# Arduino_PC104_Adapter.net
KiCad netlist of a schematic drawn in Altium Designer
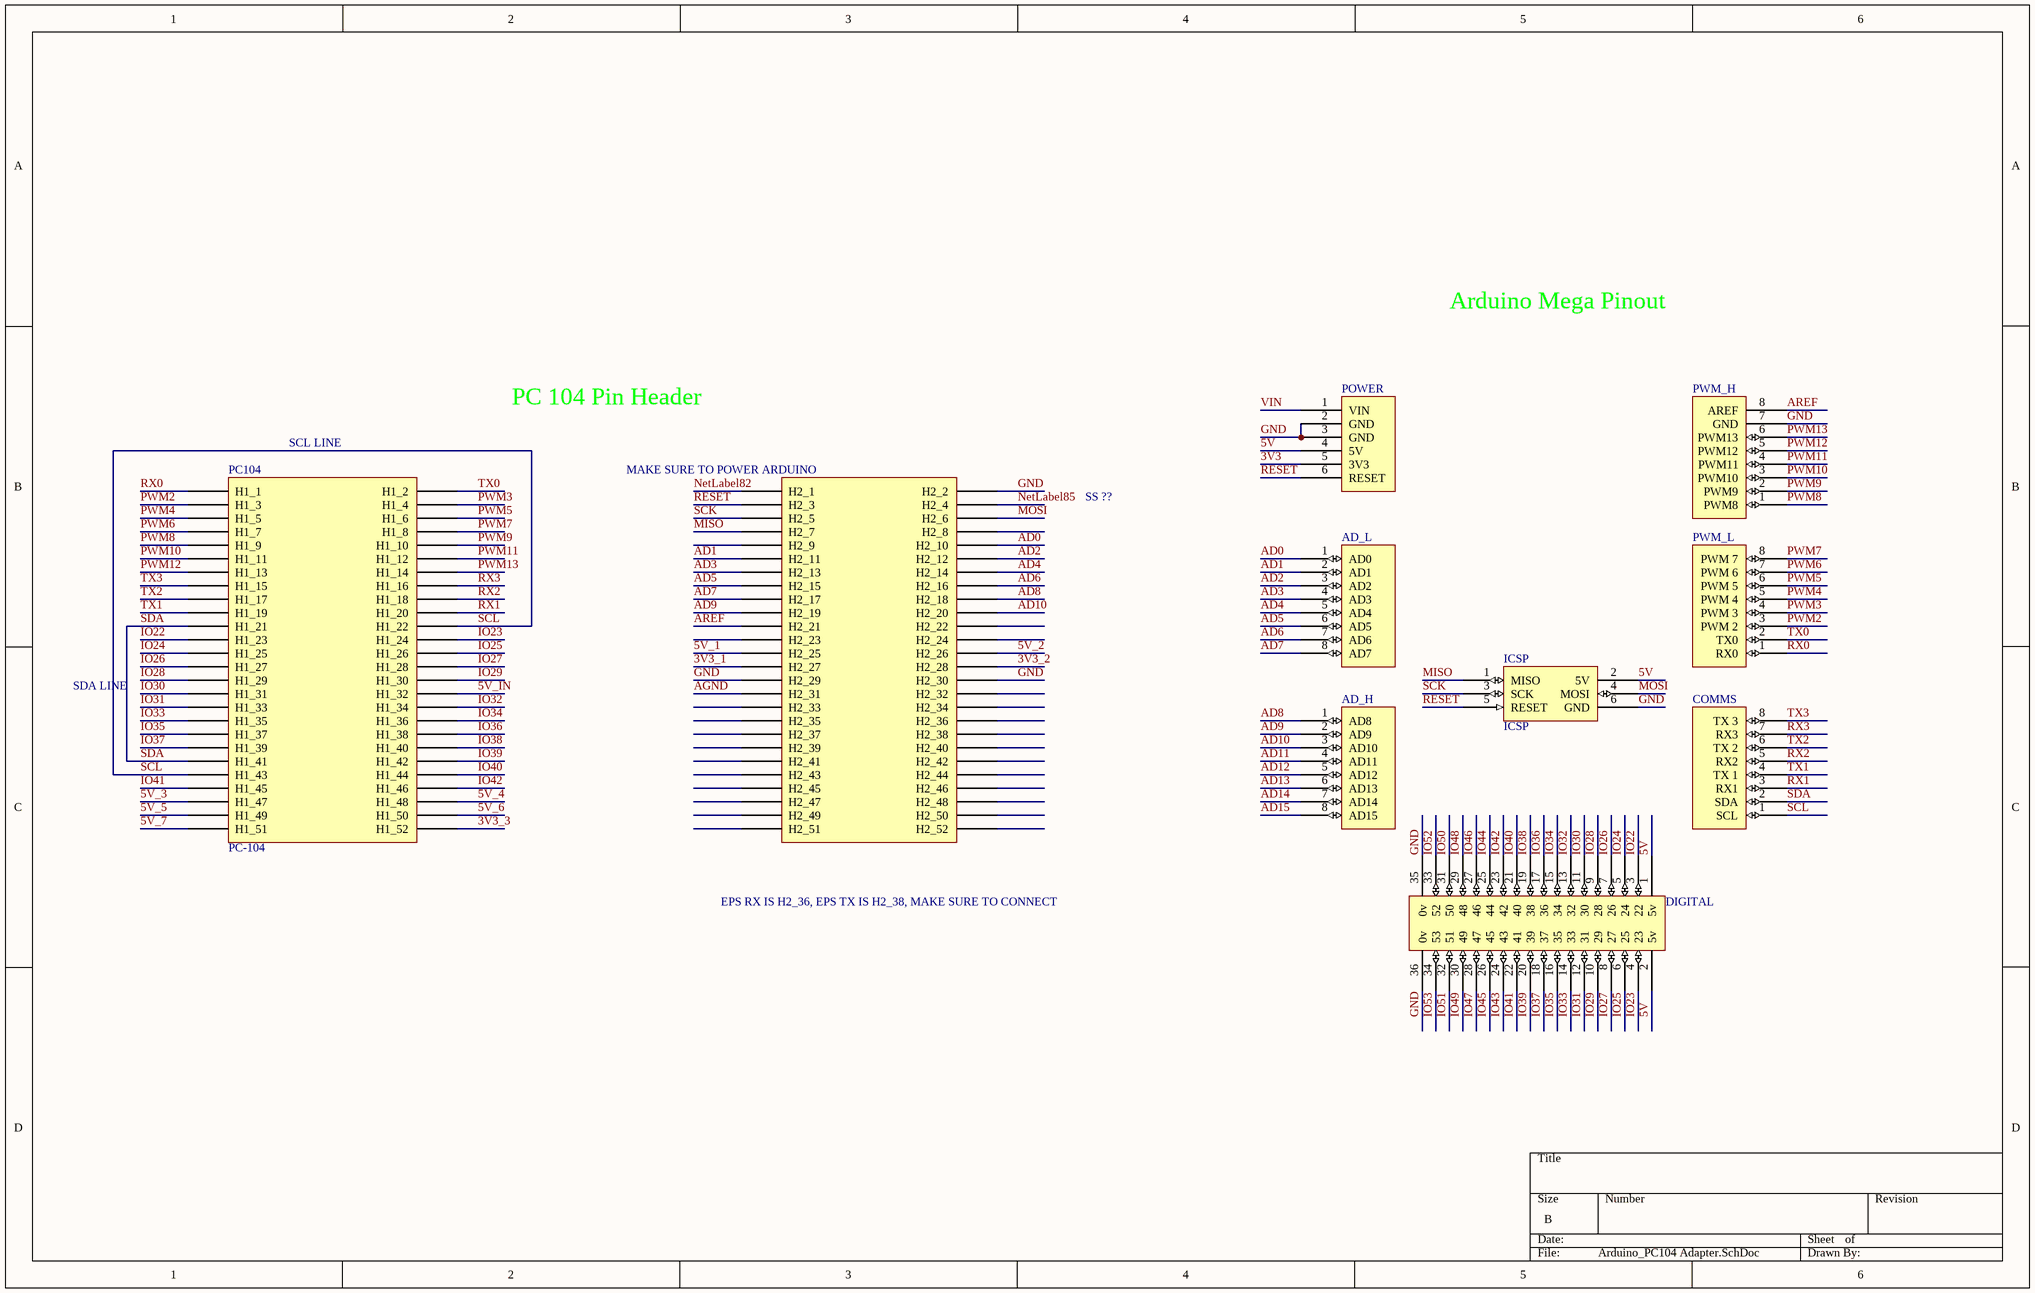
[diagram p0: Arduino_PC104 Adapter.SchDoc]

(export (version "E")
  (design (tool "Eeschema 10.0.6"))
  (components
    (comp (ref "AD_H") (value "AD_H") (footprint "Header 8x1 8.5mm") (libsource (lib "Header") (part "AD_H")))
    (comp (ref "AD_L") (value "AD_L") (footprint "Header 8x1 8.5mm") (libsource (lib "Header") (part "AD_L")))
    (comp (ref "COMMS")
      (value "Communication")
      (footprint "Header 8x1 8.5mm")
      (libsource (lib "Header") (part "Communication"))
    )
    (comp (ref "DIGITAL")
      (value "IO_36")
      (footprint "HEADER 36X 8MM")
      (libsource (lib "Header") (part "IO_36"))
    )
    (comp (ref "ICSP") (value "ICSP") (footprint "ICSP") (libsource (lib "Header") (part "ICSP")))
    (comp (ref "PC104")
      (value "PC-104")
      (footprint "PC-104FOOTPRINT")
      (libsource (lib "AdapterBoard") (part "PC-104"))
    )
    (comp (ref "POWER")
      (value "POWER")
      (footprint "Header 6x1 8.5mm")
      (libsource (lib "Header") (part "POWER"))
    )
    (comp (ref "PWM_H")
      (value "PWM_H")
      (footprint "Header 8x1 8.5mm")
      (libsource (lib "Header") (part "PWM_H"))
    )
    (comp (ref "PWM_L")
      (value "PWM_L")
      (footprint "Header 8x1 8.5mm")
      (libsource (lib "Header") (part "PWM_L"))
    )
  )
  (nets
    (net (code "1") (name "/3V3") (class "Default")
      (node (ref "POWER") (pin "5") (pinfunction "3V3_5") (pintype "power_in"))
    )
    (net (code "2") (name "/3V3_1") (class "Default")
      (node (ref "PC104") (pin "H2_27") (pinfunction "H2_27_H2_27") (pintype "passive"))
    )
    (net (code "3") (name "/3V3_2") (class "Default")
      (node (ref "PC104") (pin "H2_28") (pinfunction "H2_28_H2_28") (pintype "passive"))
    )
    (net (code "4") (name "/3V3_3") (class "Default")
      (node (ref "PC104") (pin "H1_52") (pinfunction "H1_52_H1_52") (pintype "passive"))
    )
    (net (code "5") (name "/5V") (class "Default")
      (node (ref "DIGITAL") (pin "1") (pinfunction "5v_1") (pintype "power_in"))
      (node (ref "DIGITAL") (pin "2") (pinfunction "5v_2") (pintype "power_in"))
      (node (ref "ICSP") (pin "2") (pinfunction "5V_2") (pintype "power_in"))
      (node (ref "POWER") (pin "4") (pinfunction "5V_4") (pintype "power_in"))
    )
    (net (code "6") (name "/5V_1") (class "Default")
      (node (ref "PC104") (pin "H2_25") (pinfunction "H2_25_H2_25") (pintype "passive"))
    )
    (net (code "7") (name "/5V_2") (class "Default")
      (node (ref "PC104") (pin "H2_26") (pinfunction "H2_26_H2_26") (pintype "passive"))
    )
    (net (code "8") (name "/5V_3") (class "Default")
      (node (ref "PC104") (pin "H1_47") (pinfunction "H1_47_H1_47") (pintype "passive"))
    )
    (net (code "9") (name "/5V_4") (class "Default")
      (node (ref "PC104") (pin "H1_48") (pinfunction "H1_48_H1_48") (pintype "passive"))
    )
    (net (code "10") (name "/5V_5") (class "Default")
      (node (ref "PC104") (pin "H1_49") (pinfunction "H1_49_H1_49") (pintype "passive"))
    )
    (net (code "11") (name "/5V_6") (class "Default")
      (node (ref "PC104") (pin "H1_50") (pinfunction "H1_50_H1_50") (pintype "passive"))
    )
    (net (code "12") (name "/5V_7") (class "Default")
      (node (ref "PC104") (pin "H1_51") (pinfunction "H1_51_H1_51") (pintype "passive"))
    )
    (net (code "13") (name "/5V_IN") (class "Default")
      (node (ref "PC104") (pin "H1_32") (pinfunction "H1_32_H1_32") (pintype "passive"))
    )
    (net (code "14") (name "/AD0") (class "Default")
      (node (ref "AD_L") (pin "1") (pinfunction "AD0_1") (pintype "bidirectional"))
      (node (ref "PC104") (pin "H2_10") (pinfunction "H2_10_H2_10") (pintype "passive"))
    )
    (net (code "15") (name "/AD1") (class "Default")
      (node (ref "AD_L") (pin "2") (pinfunction "AD1_2") (pintype "bidirectional"))
      (node (ref "PC104") (pin "H2_11") (pinfunction "H2_11_H2_11") (pintype "passive"))
    )
    (net (code "16") (name "/AD2") (class "Default")
      (node (ref "AD_L") (pin "3") (pinfunction "AD2_3") (pintype "bidirectional"))
      (node (ref "PC104") (pin "H2_12") (pinfunction "H2_12_H2_12") (pintype "passive"))
    )
    (net (code "17") (name "/AD3") (class "Default")
      (node (ref "AD_L") (pin "4") (pinfunction "AD3_4") (pintype "bidirectional"))
      (node (ref "PC104") (pin "H2_13") (pinfunction "H2_13_H2_13") (pintype "passive"))
    )
    (net (code "18") (name "/AD4") (class "Default")
      (node (ref "AD_L") (pin "5") (pinfunction "AD4_5") (pintype "bidirectional"))
      (node (ref "PC104") (pin "H2_14") (pinfunction "H2_14_H2_14") (pintype "passive"))
    )
    (net (code "19") (name "/AD5") (class "Default")
      (node (ref "AD_L") (pin "6") (pinfunction "AD5_6") (pintype "bidirectional"))
      (node (ref "PC104") (pin "H2_15") (pinfunction "H2_15_H2_15") (pintype "passive"))
    )
    (net (code "20") (name "/AD6") (class "Default")
      (node (ref "AD_L") (pin "7") (pinfunction "AD6_7") (pintype "bidirectional"))
      (node (ref "PC104") (pin "H2_16") (pinfunction "H2_16_H2_16") (pintype "passive"))
    )
    (net (code "21") (name "/AD7") (class "Default")
      (node (ref "AD_L") (pin "8") (pinfunction "AD7_8") (pintype "bidirectional"))
      (node (ref "PC104") (pin "H2_17") (pinfunction "H2_17_H2_17") (pintype "passive"))
    )
    (net (code "22") (name "/AD8") (class "Default")
      (node (ref "AD_H") (pin "1") (pinfunction "AD8_1") (pintype "bidirectional"))
      (node (ref "PC104") (pin "H2_18") (pinfunction "H2_18_H2_18") (pintype "passive"))
    )
    (net (code "23") (name "/AD9") (class "Default")
      (node (ref "AD_H") (pin "2") (pinfunction "AD9_2") (pintype "bidirectional"))
      (node (ref "PC104") (pin "H2_19") (pinfunction "H2_19_H2_19") (pintype "passive"))
    )
    (net (code "24") (name "/AD10") (class "Default")
      (node (ref "AD_H") (pin "3") (pinfunction "AD10_3") (pintype "bidirectional"))
      (node (ref "PC104") (pin "H2_20") (pinfunction "H2_20_H2_20") (pintype "passive"))
    )
    (net (code "25") (name "/AD11") (class "Default")
      (node (ref "AD_H") (pin "4") (pinfunction "AD11_4") (pintype "bidirectional"))
    )
    (net (code "26") (name "/AD12") (class "Default")
      (node (ref "AD_H") (pin "5") (pinfunction "AD12_5") (pintype "bidirectional"))
    )
    (net (code "27") (name "/AD13") (class "Default")
      (node (ref "AD_H") (pin "6") (pinfunction "AD13_6") (pintype "bidirectional"))
    )
    (net (code "28") (name "/AD14") (class "Default")
      (node (ref "AD_H") (pin "7") (pinfunction "AD14_7") (pintype "bidirectional"))
    )
    (net (code "29") (name "/AD15") (class "Default")
      (node (ref "AD_H") (pin "8") (pinfunction "AD15_8") (pintype "bidirectional"))
    )
    (net (code "30") (name "/AGND") (class "Default")
      (node (ref "PC104") (pin "H2_31") (pinfunction "H2_31_H2_31") (pintype "passive"))
    )
    (net (code "31") (name "/AREF") (class "Default")
      (node (ref "PC104") (pin "H2_21") (pinfunction "H2_21_H2_21") (pintype "passive"))
      (node (ref "PWM_H") (pin "8") (pinfunction "AREF_8") (pintype "passive"))
    )
    (net (code "32") (name "/GND") (class "Default")
      (node (ref "DIGITAL") (pin "35") (pinfunction "0v_35") (pintype "power_in"))
      (node (ref "DIGITAL") (pin "36") (pinfunction "0v_36") (pintype "power_in"))
      (node (ref "ICSP") (pin "6") (pinfunction "GND_6") (pintype "power_in"))
      (node (ref "PC104") (pin "H2_2") (pinfunction "H2_2_H2_2") (pintype "passive"))
      (node (ref "PC104") (pin "H2_29") (pinfunction "H2_29_H2_29") (pintype "passive"))
      (node (ref "PC104") (pin "H2_30") (pinfunction "H2_30_H2_30") (pintype "passive"))
      (node (ref "POWER") (pin "2") (pinfunction "GND_2") (pintype "power_in"))
      (node (ref "POWER") (pin "3") (pinfunction "GND_3") (pintype "power_in"))
      (node (ref "PWM_H") (pin "7") (pinfunction "GND_7") (pintype "power_in"))
    )
    (net (code "33") (name "/IO22") (class "Default")
      (node (ref "DIGITAL") (pin "3") (pinfunction "22_3") (pintype "bidirectional"))
      (node (ref "PC104") (pin "H1_23") (pinfunction "H1_23_H1_23") (pintype "passive"))
    )
    (net (code "34") (name "/IO23") (class "Default")
      (node (ref "DIGITAL") (pin "4") (pinfunction "23_4") (pintype "bidirectional"))
      (node (ref "PC104") (pin "H1_24") (pinfunction "H1_24_H1_24") (pintype "passive"))
    )
    (net (code "35") (name "/IO24") (class "Default")
      (node (ref "DIGITAL") (pin "5") (pinfunction "24_5") (pintype "bidirectional"))
      (node (ref "PC104") (pin "H1_25") (pinfunction "H1_25_H1_25") (pintype "passive"))
    )
    (net (code "36") (name "/IO25") (class "Default")
      (node (ref "DIGITAL") (pin "6") (pinfunction "25_6") (pintype "bidirectional"))
      (node (ref "PC104") (pin "H1_26") (pinfunction "H1_26_H1_26") (pintype "passive"))
    )
    (net (code "37") (name "/IO26") (class "Default")
      (node (ref "DIGITAL") (pin "7") (pinfunction "26_7") (pintype "bidirectional"))
      (node (ref "PC104") (pin "H1_27") (pinfunction "H1_27_H1_27") (pintype "passive"))
    )
    (net (code "38") (name "/IO27") (class "Default")
      (node (ref "DIGITAL") (pin "8") (pinfunction "27_8") (pintype "bidirectional"))
      (node (ref "PC104") (pin "H1_28") (pinfunction "H1_28_H1_28") (pintype "passive"))
    )
    (net (code "39") (name "/IO28") (class "Default")
      (node (ref "DIGITAL") (pin "9") (pinfunction "28_9") (pintype "bidirectional"))
      (node (ref "PC104") (pin "H1_29") (pinfunction "H1_29_H1_29") (pintype "passive"))
    )
    (net (code "40") (name "/IO29") (class "Default")
      (node (ref "DIGITAL") (pin "10") (pinfunction "29_10") (pintype "bidirectional"))
      (node (ref "PC104") (pin "H1_30") (pinfunction "H1_30_H1_30") (pintype "passive"))
    )
    (net (code "41") (name "/IO30") (class "Default")
      (node (ref "DIGITAL") (pin "11") (pinfunction "30_11") (pintype "bidirectional"))
      (node (ref "PC104") (pin "H1_31") (pinfunction "H1_31_H1_31") (pintype "passive"))
    )
    (net (code "42") (name "/IO31") (class "Default")
      (node (ref "DIGITAL") (pin "12") (pinfunction "31_12") (pintype "bidirectional"))
      (node (ref "PC104") (pin "H1_33") (pinfunction "H1_33_H1_33") (pintype "passive"))
    )
    (net (code "43") (name "/IO32") (class "Default")
      (node (ref "DIGITAL") (pin "13") (pinfunction "32_13") (pintype "bidirectional"))
      (node (ref "PC104") (pin "H1_34") (pinfunction "H1_34_H1_34") (pintype "passive"))
    )
    (net (code "44") (name "/IO33") (class "Default")
      (node (ref "DIGITAL") (pin "14") (pinfunction "33_14") (pintype "bidirectional"))
      (node (ref "PC104") (pin "H1_35") (pinfunction "H1_35_H1_35") (pintype "passive"))
    )
    (net (code "45") (name "/IO34") (class "Default")
      (node (ref "DIGITAL") (pin "15") (pinfunction "34_15") (pintype "bidirectional"))
      (node (ref "PC104") (pin "H1_36") (pinfunction "H1_36_H1_36") (pintype "passive"))
    )
    (net (code "46") (name "/IO35") (class "Default")
      (node (ref "DIGITAL") (pin "16") (pinfunction "35_16") (pintype "bidirectional"))
      (node (ref "PC104") (pin "H1_37") (pinfunction "H1_37_H1_37") (pintype "passive"))
    )
    (net (code "47") (name "/IO36") (class "Default")
      (node (ref "DIGITAL") (pin "17") (pinfunction "36_17") (pintype "bidirectional"))
      (node (ref "PC104") (pin "H1_38") (pinfunction "H1_38_H1_38") (pintype "passive"))
    )
    (net (code "48") (name "/IO37") (class "Default")
      (node (ref "DIGITAL") (pin "18") (pinfunction "37_18") (pintype "bidirectional"))
      (node (ref "PC104") (pin "H1_39") (pinfunction "H1_39_H1_39") (pintype "passive"))
    )
    (net (code "49") (name "/IO38") (class "Default")
      (node (ref "DIGITAL") (pin "19") (pinfunction "38_19") (pintype "bidirectional"))
      (node (ref "PC104") (pin "H1_40") (pinfunction "H1_40_H1_40") (pintype "passive"))
    )
    (net (code "50") (name "/IO39") (class "Default")
      (node (ref "DIGITAL") (pin "20") (pinfunction "39_20") (pintype "bidirectional"))
      (node (ref "PC104") (pin "H1_42") (pinfunction "H1_42_H1_42") (pintype "passive"))
    )
    (net (code "51") (name "/IO40") (class "Default")
      (node (ref "DIGITAL") (pin "21") (pinfunction "40_21") (pintype "bidirectional"))
      (node (ref "PC104") (pin "H1_44") (pinfunction "H1_44_H1_44") (pintype "passive"))
    )
    (net (code "52") (name "/IO41") (class "Default")
      (node (ref "DIGITAL") (pin "22") (pinfunction "41_22") (pintype "bidirectional"))
      (node (ref "PC104") (pin "H1_45") (pinfunction "H1_45_H1_45") (pintype "passive"))
    )
    (net (code "53") (name "/IO42") (class "Default")
      (node (ref "DIGITAL") (pin "23") (pinfunction "42_23") (pintype "bidirectional"))
      (node (ref "PC104") (pin "H1_46") (pinfunction "H1_46_H1_46") (pintype "passive"))
    )
    (net (code "54") (name "/IO43") (class "Default")
      (node (ref "DIGITAL") (pin "24") (pinfunction "43_24") (pintype "bidirectional"))
    )
    (net (code "55") (name "/IO44") (class "Default")
      (node (ref "DIGITAL") (pin "25") (pinfunction "44_25") (pintype "bidirectional"))
    )
    (net (code "56") (name "/IO45") (class "Default")
      (node (ref "DIGITAL") (pin "26") (pinfunction "45_26") (pintype "bidirectional"))
    )
    (net (code "57") (name "/IO46") (class "Default")
      (node (ref "DIGITAL") (pin "27") (pinfunction "46_27") (pintype "bidirectional"))
    )
    (net (code "58") (name "/IO47") (class "Default")
      (node (ref "DIGITAL") (pin "28") (pinfunction "47_28") (pintype "bidirectional"))
    )
    (net (code "59") (name "/IO48") (class "Default")
      (node (ref "DIGITAL") (pin "29") (pinfunction "48_29") (pintype "bidirectional"))
    )
    (net (code "60") (name "/IO49") (class "Default")
      (node (ref "DIGITAL") (pin "30") (pinfunction "49_30") (pintype "bidirectional"))
    )
    (net (code "61") (name "/IO50") (class "Default")
      (node (ref "DIGITAL") (pin "31") (pinfunction "50_31") (pintype "bidirectional"))
    )
    (net (code "62") (name "/IO51") (class "Default")
      (node (ref "DIGITAL") (pin "32") (pinfunction "51_32") (pintype "bidirectional"))
    )
    (net (code "63") (name "/IO52") (class "Default")
      (node (ref "DIGITAL") (pin "33") (pinfunction "52_33") (pintype "bidirectional"))
    )
    (net (code "64") (name "/IO53") (class "Default")
      (node (ref "DIGITAL") (pin "34") (pinfunction "53_34") (pintype "bidirectional"))
    )
    (net (code "65") (name "/MISO") (class "Default")
      (node (ref "ICSP") (pin "1") (pinfunction "MISO_1") (pintype "bidirectional"))
      (node (ref "PC104") (pin "H2_7") (pinfunction "H2_7_H2_7") (pintype "passive"))
    )
    (net (code "66") (name "/MOSI") (class "Default")
      (node (ref "ICSP") (pin "4") (pinfunction "MOSI_4") (pintype "bidirectional"))
      (node (ref "PC104") (pin "H2_6") (pinfunction "H2_6_H2_6") (pintype "passive"))
    )
    (net (code "67") (name "/NetLabel82") (class "Default")
      (node (ref "PC104") (pin "H2_1") (pinfunction "H2_1_H2_1") (pintype "passive"))
    )
    (net (code "68") (name "/NetLabel85") (class "Default")
      (node (ref "PC104") (pin "H2_4") (pinfunction "H2_4_H2_4") (pintype "passive"))
    )
    (net (code "69") (name "/PWM2") (class "Default")
      (node (ref "PC104") (pin "H1_3") (pinfunction "H1_3_H1_3") (pintype "tri_state"))
      (node (ref "PWM_L") (pin "3") (pinfunction "PWM_2_3") (pintype "bidirectional"))
    )
    (net (code "70") (name "/PWM3") (class "Default")
      (node (ref "PC104") (pin "H1_4") (pinfunction "H1_4_H1_4") (pintype "passive"))
      (node (ref "PWM_L") (pin "4") (pinfunction "PWM_3_4") (pintype "bidirectional"))
    )
    (net (code "71") (name "/PWM4") (class "Default")
      (node (ref "PC104") (pin "H1_5") (pinfunction "H1_5_H1_5") (pintype "passive"))
      (node (ref "PWM_L") (pin "5") (pinfunction "PWM_4_5") (pintype "bidirectional"))
    )
    (net (code "72") (name "/PWM5") (class "Default")
      (node (ref "PC104") (pin "H1_6") (pinfunction "H1_6_H1_6") (pintype "passive"))
      (node (ref "PWM_L") (pin "6") (pinfunction "PWM_5_6") (pintype "bidirectional"))
    )
    (net (code "73") (name "/PWM6") (class "Default")
      (node (ref "PC104") (pin "H1_7") (pinfunction "H1_7_H1_7") (pintype "passive"))
      (node (ref "PWM_L") (pin "7") (pinfunction "PWM_6_7") (pintype "bidirectional"))
    )
    (net (code "74") (name "/PWM7") (class "Default")
      (node (ref "PC104") (pin "H1_8") (pinfunction "H1_8_H1_8") (pintype "passive"))
      (node (ref "PWM_L") (pin "8") (pinfunction "PWM_7_8") (pintype "bidirectional"))
    )
    (net (code "75") (name "/PWM8") (class "Default")
      (node (ref "PC104") (pin "H1_9") (pinfunction "H1_9_H1_9") (pintype "passive"))
      (node (ref "PWM_H") (pin "1") (pinfunction "PWM8_1") (pintype "bidirectional"))
    )
    (net (code "76") (name "/PWM9") (class "Default")
      (node (ref "PC104") (pin "H1_10") (pinfunction "H1_10_H1_10") (pintype "passive"))
      (node (ref "PWM_H") (pin "2") (pinfunction "PWM9_2") (pintype "bidirectional"))
    )
    (net (code "77") (name "/PWM10") (class "Default")
      (node (ref "PC104") (pin "H1_11") (pinfunction "H1_11_H1_11") (pintype "passive"))
      (node (ref "PWM_H") (pin "3") (pinfunction "PWM10_3") (pintype "bidirectional"))
    )
    (net (code "78") (name "/PWM11") (class "Default")
      (node (ref "PC104") (pin "H1_12") (pinfunction "H1_12_H1_12") (pintype "passive"))
      (node (ref "PWM_H") (pin "4") (pinfunction "PWM11_4") (pintype "bidirectional"))
    )
    (net (code "79") (name "/PWM12") (class "Default")
      (node (ref "PC104") (pin "H1_13") (pinfunction "H1_13_H1_13") (pintype "passive"))
      (node (ref "PWM_H") (pin "5") (pinfunction "PWM12_5") (pintype "bidirectional"))
    )
    (net (code "80") (name "/PWM13") (class "Default")
      (node (ref "PC104") (pin "H1_14") (pinfunction "H1_14_H1_14") (pintype "passive"))
      (node (ref "PWM_H") (pin "6") (pinfunction "PWM13_6") (pintype "bidirectional"))
    )
    (net (code "81") (name "/RESET") (class "Default")
      (node (ref "ICSP") (pin "5") (pinfunction "RESET_5") (pintype "input"))
      (node (ref "PC104") (pin "H2_3") (pinfunction "H2_3_H2_3") (pintype "passive"))
      (node (ref "POWER") (pin "6") (pinfunction "RESET_6") (pintype "passive"))
    )
    (net (code "82") (name "/RX0") (class "Default")
      (node (ref "PC104") (pin "H1_1") (pinfunction "H1_1_H1_1") (pintype "passive"))
      (node (ref "PWM_L") (pin "1") (pinfunction "RX0_1") (pintype "bidirectional"))
    )
    (net (code "83") (name "/RX1") (class "Default")
      (node (ref "COMMS") (pin "3") (pinfunction "RX1_3") (pintype "bidirectional"))
      (node (ref "PC104") (pin "H1_20") (pinfunction "H1_20_H1_20") (pintype "passive"))
    )
    (net (code "84") (name "/RX2") (class "Default")
      (node (ref "COMMS") (pin "5") (pinfunction "RX2_5") (pintype "bidirectional"))
      (node (ref "PC104") (pin "H1_18") (pinfunction "H1_18_H1_18") (pintype "passive"))
    )
    (net (code "85") (name "/RX3") (class "Default")
      (node (ref "COMMS") (pin "7") (pinfunction "RX3_7") (pintype "bidirectional"))
      (node (ref "PC104") (pin "H1_16") (pinfunction "H1_16_H1_16") (pintype "passive"))
    )
    (net (code "86") (name "/SCK") (class "Default")
      (node (ref "ICSP") (pin "3") (pinfunction "SCK_3") (pintype "bidirectional"))
      (node (ref "PC104") (pin "H2_5") (pinfunction "H2_5_H2_5") (pintype "passive"))
    )
    (net (code "87") (name "/SCL") (class "Default")
      (node (ref "COMMS") (pin "1") (pinfunction "SCL_1") (pintype "bidirectional"))
      (node (ref "PC104") (pin "H1_22") (pinfunction "H1_22_H1_22") (pintype "passive"))
      (node (ref "PC104") (pin "H1_43") (pinfunction "H1_43_H1_43") (pintype "passive"))
    )
    (net (code "88") (name "/SDA") (class "Default")
      (node (ref "COMMS") (pin "2") (pinfunction "SDA_2") (pintype "bidirectional"))
      (node (ref "PC104") (pin "H1_21") (pinfunction "H1_21_H1_21") (pintype "passive"))
      (node (ref "PC104") (pin "H1_41") (pinfunction "H1_41_H1_41") (pintype "passive"))
    )
    (net (code "89") (name "/TX0") (class "Default")
      (node (ref "PC104") (pin "H1_2") (pinfunction "H1_2_H1_2") (pintype "passive"))
      (node (ref "PWM_L") (pin "2") (pinfunction "TX0_2") (pintype "bidirectional"))
    )
    (net (code "90") (name "/TX1") (class "Default")
      (node (ref "COMMS") (pin "4") (pinfunction "TX_1_4") (pintype "bidirectional"))
      (node (ref "PC104") (pin "H1_19") (pinfunction "H1_19_H1_19") (pintype "passive"))
    )
    (net (code "91") (name "/TX2") (class "Default")
      (node (ref "COMMS") (pin "6") (pinfunction "TX_2_6") (pintype "bidirectional"))
      (node (ref "PC104") (pin "H1_17") (pinfunction "H1_17_H1_17") (pintype "passive"))
    )
    (net (code "92") (name "/TX3") (class "Default")
      (node (ref "COMMS") (pin "8") (pinfunction "TX_3_8") (pintype "bidirectional"))
      (node (ref "PC104") (pin "H1_15") (pinfunction "H1_15_H1_15") (pintype "passive"))
    )
    (net (code "93") (name "/VIN") (class "Default")
      (node (ref "POWER") (pin "1") (pinfunction "VIN_1") (pintype "power_in"))
    )
    (net (code "94") (name "unconnected-(PC104-PadH2_8)") (class "Default")
      (node (ref "PC104") (pin "H2_8") (pinfunction "H2_8_H2_8") (pintype "passive"))
    )
    (net (code "95") (name "unconnected-(PC104-PadH2_9)") (class "Default")
      (node (ref "PC104") (pin "H2_9") (pinfunction "H2_9_H2_9") (pintype "passive"))
    )
    (net (code "96") (name "unconnected-(PC104-PadH2_22)") (class "Default")
      (node (ref "PC104") (pin "H2_22") (pinfunction "H2_22_H2_22") (pintype "passive"))
    )
    (net (code "97") (name "unconnected-(PC104-PadH2_23)") (class "Default")
      (node (ref "PC104") (pin "H2_23") (pinfunction "H2_23_H2_23") (pintype "passive"))
    )
    (net (code "98") (name "unconnected-(PC104-PadH2_24)") (class "Default")
      (node (ref "PC104") (pin "H2_24") (pinfunction "H2_24_H2_24") (pintype "passive"))
    )
    (net (code "99") (name "unconnected-(PC104-PadH2_32)") (class "Default")
      (node (ref "PC104") (pin "H2_32") (pinfunction "H2_32_H2_32") (pintype "passive"))
    )
    (net (code "100") (name "unconnected-(PC104-PadH2_33)") (class "Default")
      (node (ref "PC104") (pin "H2_33") (pinfunction "H2_33_H2_33") (pintype "passive"))
    )
    (net (code "101") (name "unconnected-(PC104-PadH2_34)") (class "Default")
      (node (ref "PC104") (pin "H2_34") (pinfunction "H2_34_H2_34") (pintype "passive"))
    )
    (net (code "102") (name "unconnected-(PC104-PadH2_35)") (class "Default")
      (node (ref "PC104") (pin "H2_35") (pinfunction "H2_35_H2_35") (pintype "passive"))
    )
    (net (code "103") (name "unconnected-(PC104-PadH2_36)") (class "Default")
      (node (ref "PC104") (pin "H2_36") (pinfunction "H2_36_H2_36") (pintype "passive"))
    )
    (net (code "104") (name "unconnected-(PC104-PadH2_37)") (class "Default")
      (node (ref "PC104") (pin "H2_37") (pinfunction "H2_37_H2_37") (pintype "passive"))
    )
    (net (code "105") (name "unconnected-(PC104-PadH2_38)") (class "Default")
      (node (ref "PC104") (pin "H2_38") (pinfunction "H2_38_H2_38") (pintype "passive"))
    )
    (net (code "106") (name "unconnected-(PC104-PadH2_39)") (class "Default")
      (node (ref "PC104") (pin "H2_39") (pinfunction "H2_39_H2_39") (pintype "passive"))
    )
    (net (code "107") (name "unconnected-(PC104-PadH2_40)") (class "Default")
      (node (ref "PC104") (pin "H2_40") (pinfunction "H2_40_H2_40") (pintype "passive"))
    )
    (net (code "108") (name "unconnected-(PC104-PadH2_41)") (class "Default")
      (node (ref "PC104") (pin "H2_41") (pinfunction "H2_41_H2_41") (pintype "passive"))
    )
    (net (code "109") (name "unconnected-(PC104-PadH2_42)") (class "Default")
      (node (ref "PC104") (pin "H2_42") (pinfunction "H2_42_H2_42") (pintype "passive"))
    )
    (net (code "110") (name "unconnected-(PC104-PadH2_43)") (class "Default")
      (node (ref "PC104") (pin "H2_43") (pinfunction "H2_43_H2_43") (pintype "passive"))
    )
    (net (code "111") (name "unconnected-(PC104-PadH2_44)") (class "Default")
      (node (ref "PC104") (pin "H2_44") (pinfunction "H2_44_H2_44") (pintype "passive"))
    )
    (net (code "112") (name "unconnected-(PC104-PadH2_45)") (class "Default")
      (node (ref "PC104") (pin "H2_45") (pinfunction "H2_45_H2_45") (pintype "passive"))
    )
    (net (code "113") (name "unconnected-(PC104-PadH2_46)") (class "Default")
      (node (ref "PC104") (pin "H2_46") (pinfunction "H2_46_H2_46") (pintype "passive"))
    )
    (net (code "114") (name "unconnected-(PC104-PadH2_47)") (class "Default")
      (node (ref "PC104") (pin "H2_47") (pinfunction "H2_47_H2_47") (pintype "passive"))
    )
    (net (code "115") (name "unconnected-(PC104-PadH2_48)") (class "Default")
      (node (ref "PC104") (pin "H2_48") (pinfunction "H2_48_H2_48") (pintype "passive"))
    )
    (net (code "116") (name "unconnected-(PC104-PadH2_49)") (class "Default")
      (node (ref "PC104") (pin "H2_49") (pinfunction "H2_49_H2_49") (pintype "passive"))
    )
    (net (code "117") (name "unconnected-(PC104-PadH2_50)") (class "Default")
      (node (ref "PC104") (pin "H2_50") (pinfunction "H2_50_H2_50") (pintype "passive"))
    )
    (net (code "118") (name "unconnected-(PC104-PadH2_51)") (class "Default")
      (node (ref "PC104") (pin "H2_51") (pinfunction "H2_51_H2_51") (pintype "passive"))
    )
    (net (code "119") (name "unconnected-(PC104-PadH2_52)") (class "Default")
      (node (ref "PC104") (pin "H2_52") (pinfunction "H2_52_H2_52") (pintype "passive"))
    )
  )
)
